# core_v1-1.net
KiCad netlist of a schematic drawn in EAGLE
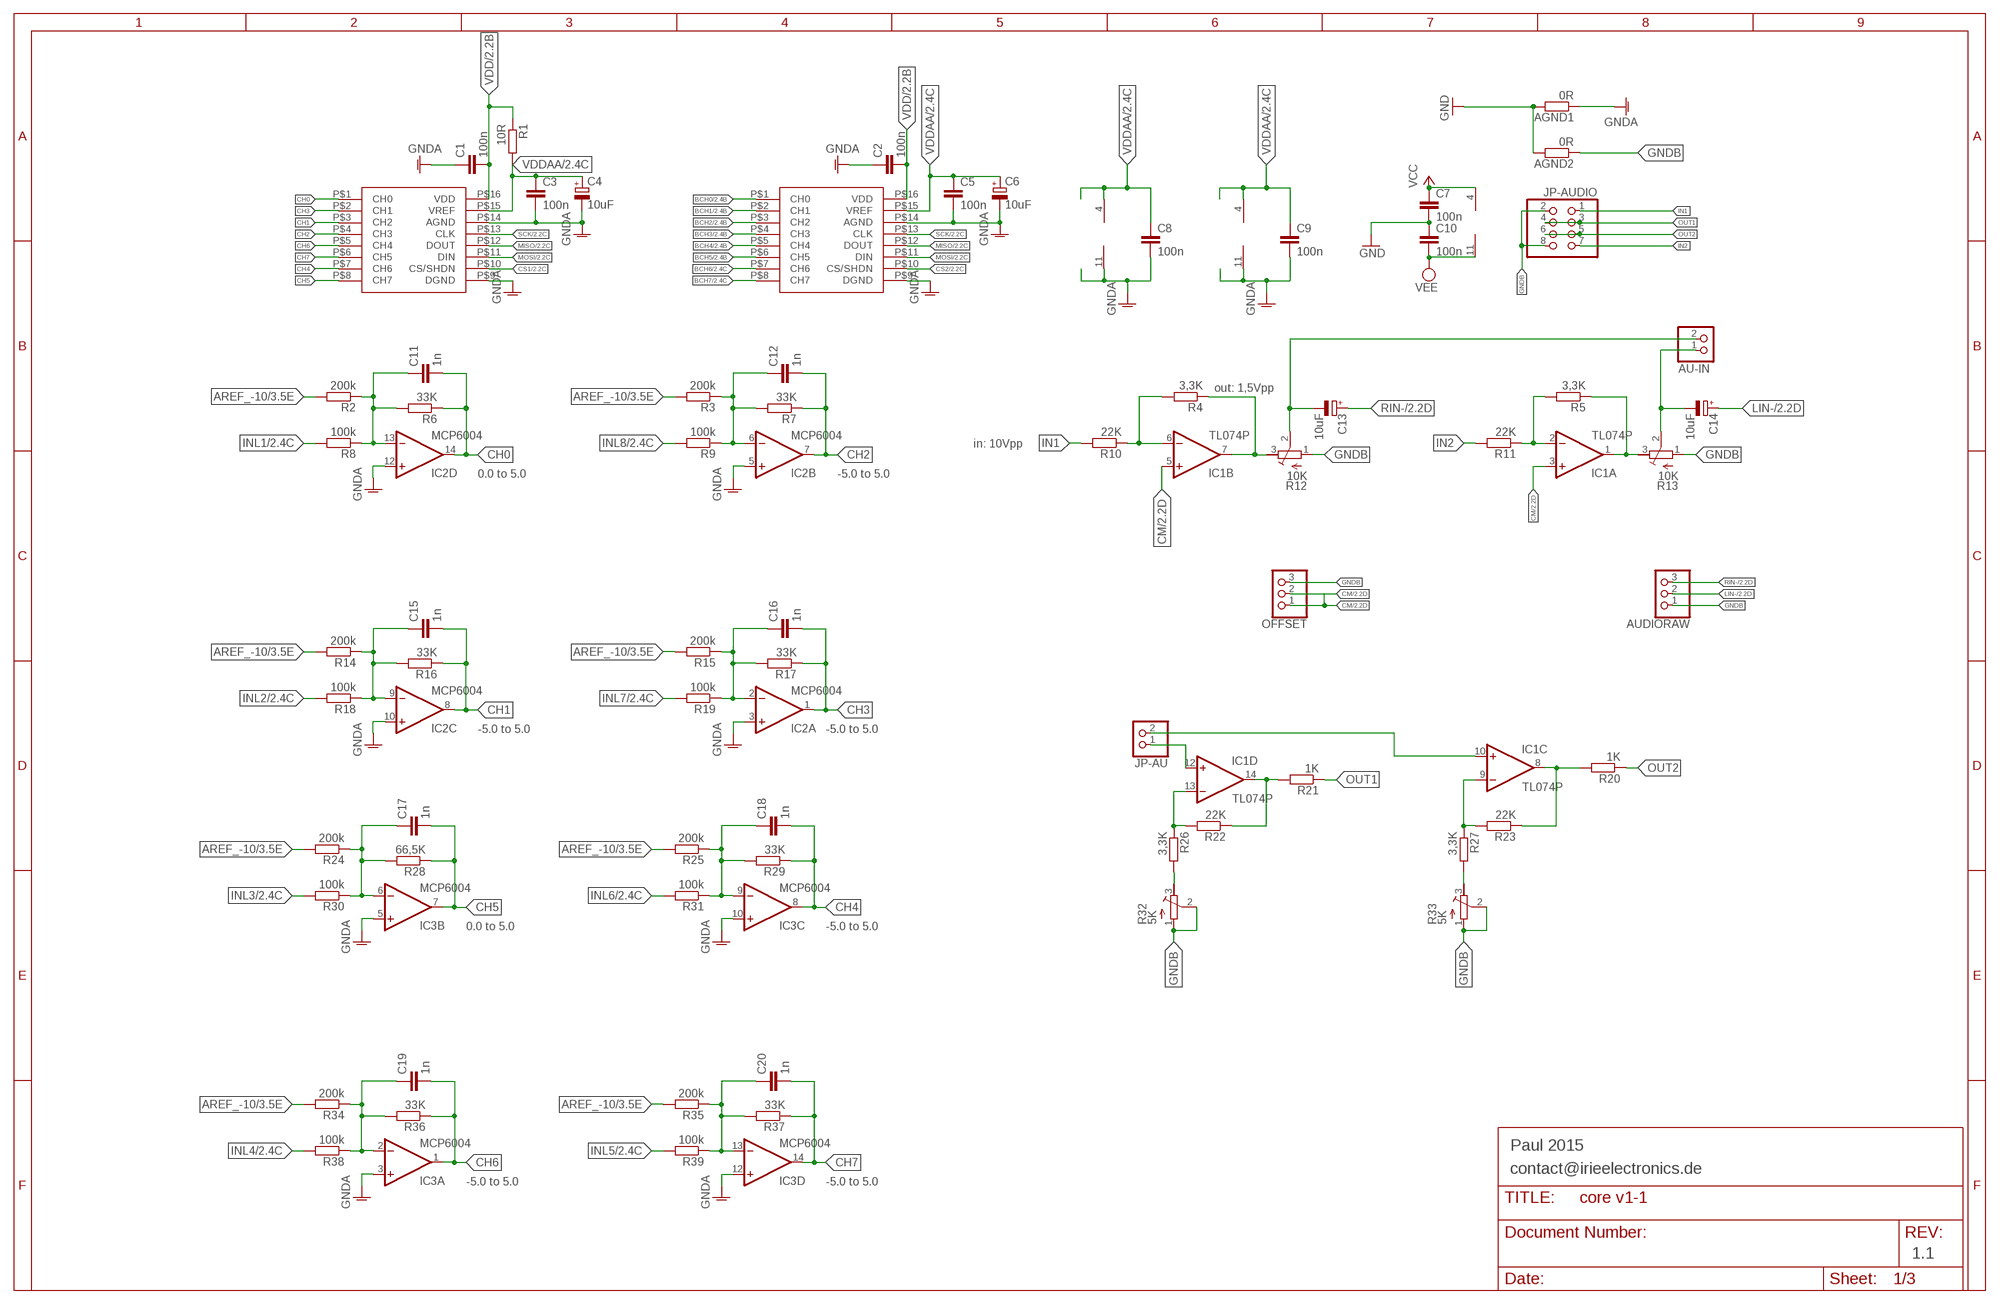
[diagram p0: schematic, sheet 1]
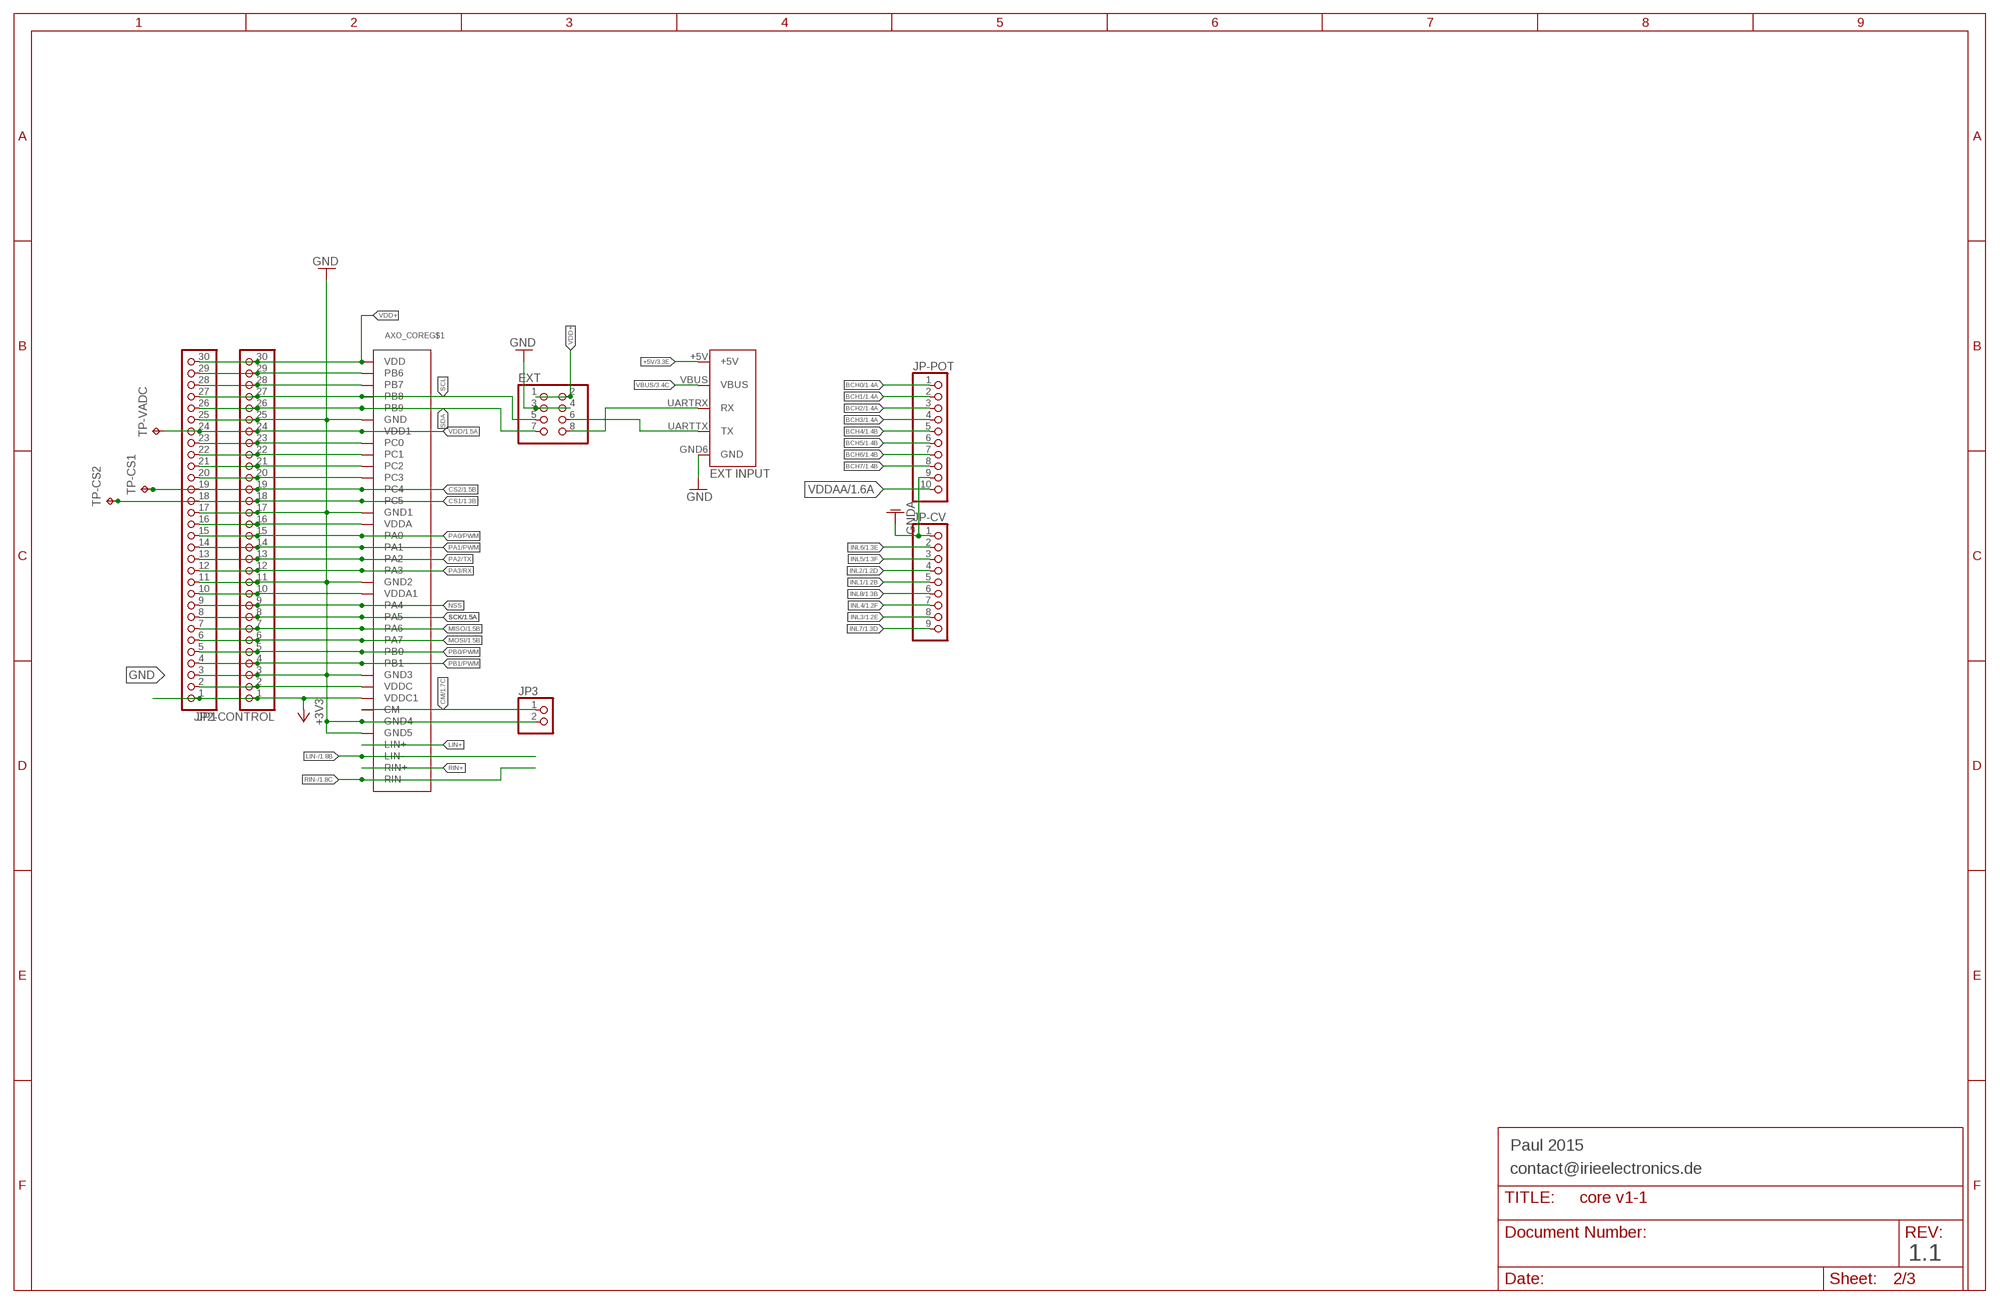
[diagram p1: schematic, sheet 2]
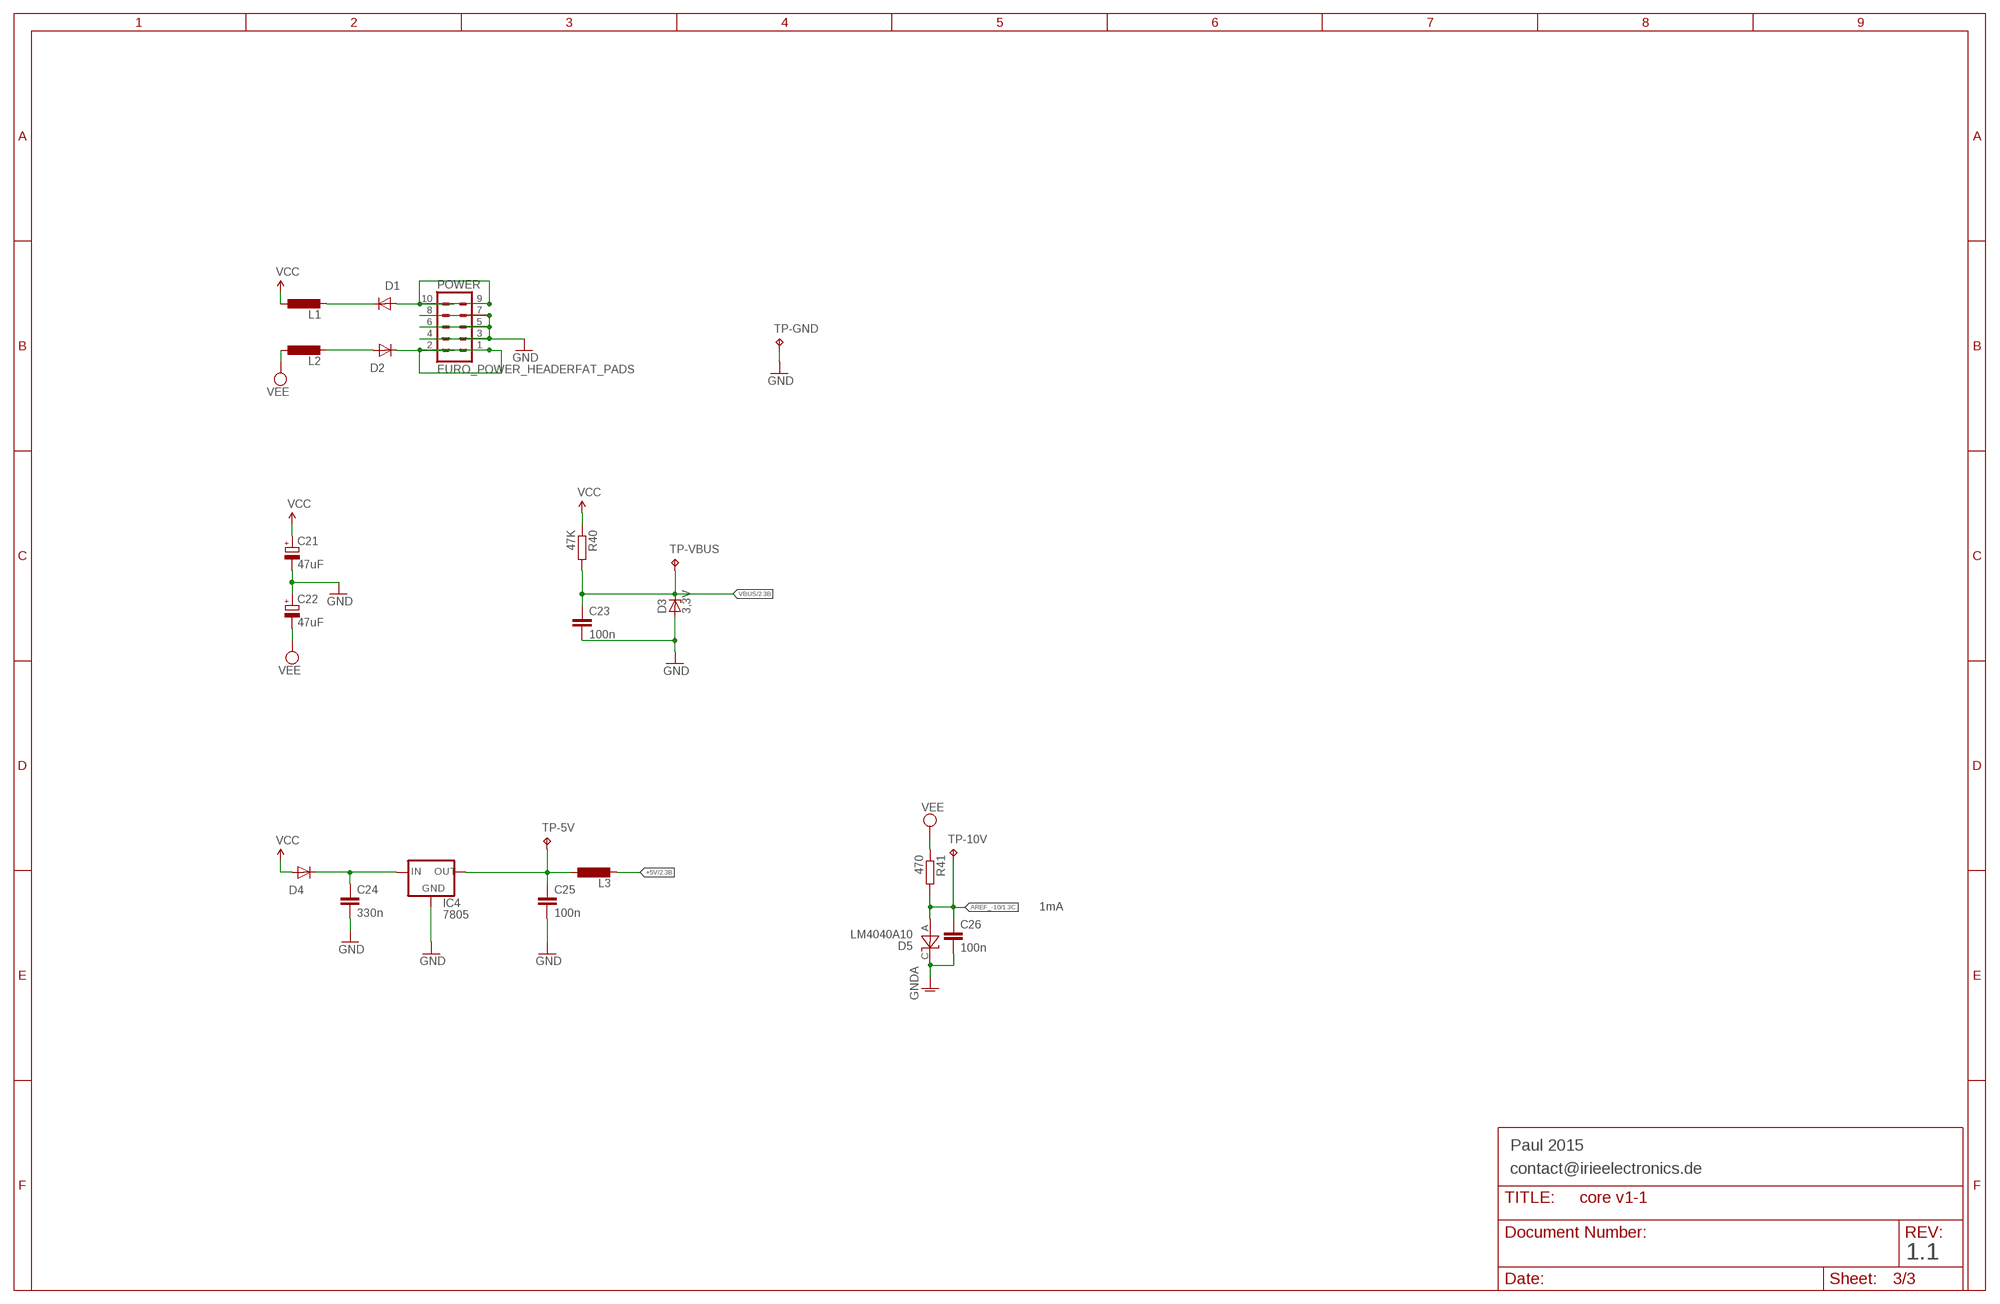
[diagram p2: schematic, sheet 3]

(export (version "E")
  (design (tool "Eeschema 10.0.6"))
  (components
    (comp (ref "C21")
      (value "47uF")
      (footprint "eagle-import:E2-5")
      (libsource (lib "eagle-import") (part "CPOL-EUE2-5"))
    )
    (comp (ref "C22")
      (value "47uF")
      (footprint "eagle-import:E2-5")
      (libsource (lib "eagle-import") (part "CPOL-EUE2-5"))
    )
    (comp (ref "C23")
      (value "100n")
      (footprint "eagle-import:C025-025X050")
      (libsource (lib "eagle-import") (part "C-EU025-025X050"))
    )
    (comp (ref "C24")
      (value "330n")
      (footprint "eagle-import:C025-025X050")
      (libsource (lib "eagle-import") (part "C-EU025-025X050"))
    )
    (comp (ref "C25")
      (value "100n")
      (footprint "eagle-import:C025-025X050")
      (libsource (lib "eagle-import") (part "C-EU025-025X050"))
    )
    (comp (ref "C26")
      (value "100n")
      (footprint "eagle-import:C025-025X050")
      (libsource (lib "eagle-import") (part "C-EU025-025X050"))
    )
    (comp (ref "D1")
      (value "1N5819")
      (footprint "eagle-import:DO35-10")
      (libsource (lib "eagle-import") (part "1N4148DO35-10"))
    )
    (comp (ref "D2")
      (value "1N5819")
      (footprint "eagle-import:DO35-10")
      (libsource (lib "eagle-import") (part "1N4148DO35-10"))
    )
    (comp (ref "D3")
      (value "3,3V")
      (footprint "eagle-import:DO35Z10")
      (libsource (lib "eagle-import") (part "1N821"))
    )
    (comp (ref "D4")
      (value "1N5819HW")
      (footprint "eagle-import:DO35-10")
      (libsource (lib "eagle-import") (part "1N4148DO35-10"))
    )
    (comp (ref "D5")
      (value "LM4040A10")
      (footprint "eagle-import:TO-92")
      (libsource (lib "eagle-import") (part "LM4040DIP"))
    )
    (comp (ref "IC4")
      (value "7805")
      (footprint "eagle-import:78MXXS")
      (libsource (lib "eagle-import") (part "78MXXS"))
    )
    (comp (ref "L1")
      (value "L-EU0207/10")
      (footprint "eagle-import:0207_10")
      (libsource (lib "eagle-import") (part "L-EU0207/10"))
    )
    (comp (ref "L2")
      (value "L-EU0207/10")
      (footprint "eagle-import:0207_10")
      (libsource (lib "eagle-import") (part "L-EU0207/10"))
    )
    (comp (ref "L3")
      (value "L-EU0207/10")
      (footprint "eagle-import:0207_10")
      (libsource (lib "eagle-import") (part "L-EU0207/10"))
    )
    (comp (ref "POWER")
      (value "EURO_POWER_HEADERFAT_PADS")
      (footprint "eagle-import:EURO_PWR_HEADER_FAT")
      (libsource (lib "eagle-import") (part "EURO_POWER_HEADERFAT_PADS"))
    )
    (comp (ref "R40")
      (value "47K")
      (footprint "eagle-import:0207_7")
      (libsource (lib "eagle-import") (part "R-EU_0207/7"))
    )
    (comp (ref "R41")
      (value "470")
      (footprint "eagle-import:0207_10")
      (libsource (lib "eagle-import") (part "R-EU_0207/10"))
    )
    (comp (ref "TP-5V")
      (value "TPTP10R")
      (footprint "eagle-import:TP10R")
      (libsource (lib "eagle-import") (part "TPTP10R"))
    )
    (comp (ref "TP-10V")
      (value "TPTP10R")
      (footprint "eagle-import:TP10R")
      (libsource (lib "eagle-import") (part "TPTP10R"))
    )
    (comp (ref "TP-GND")
      (value "TPPAD1-13")
      (footprint "eagle-import:P1-13")
      (libsource (lib "eagle-import") (part "TPPAD1-13"))
    )
    (comp (ref "TP-VBUS")
      (value "TPTP10R")
      (footprint "eagle-import:TP10R")
      (libsource (lib "eagle-import") (part "TPTP10R"))
    )
    (comp (ref "AGND1")
      (value "0R")
      (footprint "eagle-import:0207_7")
      (libsource (lib "eagle-import") (part "R-EU_0207/7"))
    )
    (comp (ref "AGND2")
      (value "0R")
      (footprint "eagle-import:0207_7")
      (libsource (lib "eagle-import") (part "R-EU_0207/7"))
    )
    (comp (ref "AU-IN")
      (value "PINHD-1X2_2.54-SMD-90°")
      (footprint "eagle-import:1X02SMD_90")
      (libsource (lib "eagle-import") (part "PINHD-1X2_2.54-SMD-90°"))
    )
    (comp (ref "AUDIORAW")
      (value "PINHD-1X3_2.54-SMD-90°")
      (footprint "eagle-import:1X03SMD_90")
      (libsource (lib "eagle-import") (part "PINHD-1X3_2.54-SMD-90°"))
    )
    (comp (ref "C1")
      (value "100n")
      (footprint "eagle-import:C025-025X050")
      (libsource (lib "eagle-import") (part "C-EU025-025X050"))
    )
    (comp (ref "C2")
      (value "100n")
      (footprint "eagle-import:C025-025X050")
      (libsource (lib "eagle-import") (part "C-EU025-025X050"))
    )
    (comp (ref "C3")
      (value "100n")
      (footprint "eagle-import:C025-025X050")
      (libsource (lib "eagle-import") (part "C-EU025-025X050"))
    )
    (comp (ref "C4")
      (value "10uF")
      (footprint "eagle-import:E1,8-4")
      (libsource (lib "eagle-import") (part "CPOL-EUE1.8-4"))
    )
    (comp (ref "C5")
      (value "100n")
      (footprint "eagle-import:C025-025X050")
      (libsource (lib "eagle-import") (part "C-EU025-025X050"))
    )
    (comp (ref "C6")
      (value "10uF")
      (footprint "eagle-import:E1,8-4")
      (libsource (lib "eagle-import") (part "CPOL-EUE1.8-4"))
    )
    (comp (ref "C7")
      (value "100n")
      (footprint "eagle-import:C025-025X050")
      (libsource (lib "eagle-import") (part "C-EU025-025X050"))
    )
    (comp (ref "C8")
      (value "100n")
      (footprint "eagle-import:C025-025X050")
      (libsource (lib "eagle-import") (part "C-EU025-025X050"))
    )
    (comp (ref "C9")
      (value "100n")
      (footprint "eagle-import:C025-025X050")
      (libsource (lib "eagle-import") (part "C-EU025-025X050"))
    )
    (comp (ref "C10")
      (value "100n")
      (footprint "eagle-import:C025-025X050")
      (libsource (lib "eagle-import") (part "C-EU025-025X050"))
    )
    (comp (ref "C11")
      (value "1n")
      (footprint "eagle-import:C050-025X075")
      (libsource (lib "eagle-import") (part "C-EU050-025X075"))
    )
    (comp (ref "C12")
      (value "1n")
      (footprint "eagle-import:C050-025X075")
      (libsource (lib "eagle-import") (part "C-EU050-025X075"))
    )
    (comp (ref "C13")
      (value "10uF")
      (footprint "eagle-import:E1,8-4")
      (libsource (lib "eagle-import") (part "CPOL-EUE1.8-4"))
    )
    (comp (ref "C14")
      (value "10uF")
      (footprint "eagle-import:E1,8-4")
      (libsource (lib "eagle-import") (part "CPOL-EUE1.8-4"))
    )
    (comp (ref "C15")
      (value "1n")
      (footprint "eagle-import:C050-025X075")
      (libsource (lib "eagle-import") (part "C-EU050-025X075"))
    )
    (comp (ref "C16")
      (value "1n")
      (footprint "eagle-import:C050-025X075")
      (libsource (lib "eagle-import") (part "C-EU050-025X075"))
    )
    (comp (ref "C17")
      (value "1n")
      (footprint "eagle-import:C050-025X075")
      (libsource (lib "eagle-import") (part "C-EU050-025X075"))
    )
    (comp (ref "C18")
      (value "1n")
      (footprint "eagle-import:C050-025X075")
      (libsource (lib "eagle-import") (part "C-EU050-025X075"))
    )
    (comp (ref "C19")
      (value "1n")
      (footprint "eagle-import:C050-025X075")
      (libsource (lib "eagle-import") (part "C-EU050-025X075"))
    )
    (comp (ref "C20")
      (value "1n")
      (footprint "eagle-import:C050-025X075")
      (libsource (lib "eagle-import") (part "C-EU050-025X075"))
    )
    (comp (ref "IC1")
      (value "TL074P")
      (footprint "eagle-import:DIL14")
      (libsource (lib "eagle-import") (part "TL074P"))
    )
    (comp (ref "IC2")
      (value "MCP6004")
      (footprint "eagle-import:DIL14")
      (libsource (lib "eagle-import") (part "TL074P"))
    )
    (comp (ref "IC3")
      (value "MCP6004")
      (footprint "eagle-import:DIL14")
      (libsource (lib "eagle-import") (part "TL074P"))
    )
    (comp (ref "JP-AU")
      (value "PINHD-1X2_2.54")
      (footprint "eagle-import:1X02")
      (libsource (lib "eagle-import") (part "PINHD-1X2_2.54"))
    )
    (comp (ref "JP-AUDIO")
      (value "PINHD-2X4_2.54")
      (footprint "eagle-import:2X04")
      (libsource (lib "eagle-import") (part "PINHD-2X4_2.54"))
    )
    (comp (ref "OFFSET")
      (value "PINHD-1X3_2.54-SMD-90°")
      (footprint "eagle-import:1X03SMD_90")
      (libsource (lib "eagle-import") (part "PINHD-1X3_2.54-SMD-90°"))
    )
    (comp (ref "R1")
      (value "10R")
      (footprint "eagle-import:0207_7")
      (libsource (lib "eagle-import") (part "R-EU_0207/7"))
    )
    (comp (ref "R2")
      (value "200k")
      (footprint "eagle-import:0207_7")
      (libsource (lib "eagle-import") (part "R-EU_0207/7"))
    )
    (comp (ref "R3")
      (value "200k")
      (footprint "eagle-import:0207_7")
      (libsource (lib "eagle-import") (part "R-EU_0207/7"))
    )
    (comp (ref "R4")
      (value "3,3K")
      (footprint "eagle-import:0207_7")
      (libsource (lib "eagle-import") (part "R-EU_0207/7"))
    )
    (comp (ref "R5")
      (value "3,3K")
      (footprint "eagle-import:0207_7")
      (libsource (lib "eagle-import") (part "R-EU_0207/7"))
    )
    (comp (ref "R6")
      (value "33K")
      (footprint "eagle-import:0207_7")
      (libsource (lib "eagle-import") (part "R-EU_0207/7"))
    )
    (comp (ref "R7")
      (value "33K")
      (footprint "eagle-import:0207_7")
      (libsource (lib "eagle-import") (part "R-EU_0207/7"))
    )
    (comp (ref "R8")
      (value "100k")
      (footprint "eagle-import:0207_7")
      (libsource (lib "eagle-import") (part "R-EU_0207/7"))
    )
    (comp (ref "R9")
      (value "100k")
      (footprint "eagle-import:0207_7")
      (libsource (lib "eagle-import") (part "R-EU_0207/7"))
    )
    (comp (ref "R10")
      (value "22K")
      (footprint "eagle-import:0207_7")
      (libsource (lib "eagle-import") (part "R-EU_0207/7"))
    )
    (comp (ref "R11")
      (value "22K")
      (footprint "eagle-import:0207_7")
      (libsource (lib "eagle-import") (part "R-EU_0207/7"))
    )
    (comp (ref "R12")
      (value "10K")
      (footprint "eagle-import:RTRIM3296P")
      (libsource (lib "eagle-import") (part "R-TRIMM3296P"))
    )
    (comp (ref "R13")
      (value "10K")
      (footprint "eagle-import:RTRIM3296P")
      (libsource (lib "eagle-import") (part "R-TRIMM3296P"))
    )
    (comp (ref "R14")
      (value "200k")
      (footprint "eagle-import:0207_7")
      (libsource (lib "eagle-import") (part "R-EU_0207/7"))
    )
    (comp (ref "R15")
      (value "200k")
      (footprint "eagle-import:0207_7")
      (libsource (lib "eagle-import") (part "R-EU_0207/7"))
    )
    (comp (ref "R16")
      (value "33K")
      (footprint "eagle-import:0207_7")
      (libsource (lib "eagle-import") (part "R-EU_0207/7"))
    )
    (comp (ref "R17")
      (value "33K")
      (footprint "eagle-import:0207_7")
      (libsource (lib "eagle-import") (part "R-EU_0207/7"))
    )
    (comp (ref "R18")
      (value "100k")
      (footprint "eagle-import:0207_7")
      (libsource (lib "eagle-import") (part "R-EU_0207/7"))
    )
    (comp (ref "R19")
      (value "100k")
      (footprint "eagle-import:0207_10")
      (libsource (lib "eagle-import") (part "R-EU_0207/10"))
    )
    (comp (ref "R20")
      (value "1K")
      (footprint "eagle-import:0207_7")
      (libsource (lib "eagle-import") (part "R-EU_0207/7"))
    )
    (comp (ref "R21")
      (value "1K")
      (footprint "eagle-import:0207_7")
      (libsource (lib "eagle-import") (part "R-EU_0207/7"))
    )
    (comp (ref "R22")
      (value "22K")
      (footprint "eagle-import:0207_10")
      (libsource (lib "eagle-import") (part "R-EU_0207/10"))
    )
    (comp (ref "R23")
      (value "22K")
      (footprint "eagle-import:0207_7")
      (libsource (lib "eagle-import") (part "R-EU_0207/7"))
    )
    (comp (ref "R24")
      (value "200k")
      (footprint "eagle-import:0207_10")
      (libsource (lib "eagle-import") (part "R-EU_0207/10"))
    )
    (comp (ref "R25")
      (value "200k")
      (footprint "eagle-import:0207_7")
      (libsource (lib "eagle-import") (part "R-EU_0207/7"))
    )
    (comp (ref "R26")
      (value "3,3K")
      (footprint "eagle-import:0207_10")
      (libsource (lib "eagle-import") (part "R-EU_0207/10"))
    )
    (comp (ref "R27")
      (value "3,3K")
      (footprint "eagle-import:0207_7")
      (libsource (lib "eagle-import") (part "R-EU_0207/7"))
    )
    (comp (ref "R28")
      (value "66,5K")
      (footprint "eagle-import:0207_7")
      (libsource (lib "eagle-import") (part "R-EU_0207/7"))
    )
    (comp (ref "R29")
      (value "33K")
      (footprint "eagle-import:0207_7")
      (libsource (lib "eagle-import") (part "R-EU_0207/7"))
    )
    (comp (ref "R30")
      (value "100k")
      (footprint "eagle-import:0207_7")
      (libsource (lib "eagle-import") (part "R-EU_0207/7"))
    )
    (comp (ref "R31")
      (value "100k")
      (footprint "eagle-import:0207_7")
      (libsource (lib "eagle-import") (part "R-EU_0207/7"))
    )
    (comp (ref "R32")
      (value "5K")
      (footprint "eagle-import:RTRIM3296P")
      (libsource (lib "eagle-import") (part "R-TRIMM3296P"))
    )
    (comp (ref "R33")
      (value "5K")
      (footprint "eagle-import:RTRIM3296P")
      (libsource (lib "eagle-import") (part "R-TRIMM3296P"))
    )
    (comp (ref "R34")
      (value "200k")
      (footprint "eagle-import:0207_10")
      (libsource (lib "eagle-import") (part "R-EU_0207/10"))
    )
    (comp (ref "R35")
      (value "200k")
      (footprint "eagle-import:0207_7")
      (libsource (lib "eagle-import") (part "R-EU_0207/7"))
    )
    (comp (ref "R36")
      (value "33K")
      (footprint "eagle-import:0207_7")
      (libsource (lib "eagle-import") (part "R-EU_0207/7"))
    )
    (comp (ref "R37")
      (value "33K")
      (footprint "eagle-import:0207_7")
      (libsource (lib "eagle-import") (part "R-EU_0207/7"))
    )
    (comp (ref "R38")
      (value "100k")
      (footprint "eagle-import:0207_7")
      (libsource (lib "eagle-import") (part "R-EU_0207/7"))
    )
    (comp (ref "R39")
      (value "100k")
      (footprint "eagle-import:0207_7")
      (libsource (lib "eagle-import") (part "R-EU_0207/7"))
    )
    (comp (ref "U$1")
      (value "MCP3208_DIP")
      (footprint "eagle-import:MCP2308")
      (libsource (lib "eagle-import") (part "MCP3208_DIP"))
    )
    (comp (ref "U$2")
      (value "MCP3208_DIP")
      (footprint "eagle-import:MCP2308")
      (libsource (lib "eagle-import") (part "MCP3208_DIP"))
    )
    (comp (ref "AXO_CORE")
      (value "AXO-CORE")
      (footprint "eagle-import:AXOLOTI-CORE")
      (libsource (lib "eagle-import") (part "AXOLOTI-CORE"))
    )
    (comp (ref "EXT")
      (value "PINHD-2X4_2.54")
      (footprint "eagle-import:2X04")
      (libsource (lib "eagle-import") (part "PINHD-2X4_2.54"))
    )
    (comp (ref "JP-CV")
      (value "PINHD-1X9_2.54")
      (footprint "eagle-import:1X09")
      (libsource (lib "eagle-import") (part "PINHD-1X9_2.54"))
    )
    (comp (ref "JP-POT")
      (value "PINHD-1X10_2.54")
      (footprint "eagle-import:1X10")
      (libsource (lib "eagle-import") (part "PINHD-1X10_2.54"))
    )
    (comp (ref "JP1")
      (value "PINHD-1X30")
      (footprint "eagle-import:1X30")
      (libsource (lib "eagle-import") (part "PINHD-1X30"))
    )
    (comp (ref "JP2-CONTROL")
      (value "PINHD-1X30")
      (footprint "eagle-import:1X30")
      (libsource (lib "eagle-import") (part "PINHD-1X30"))
    )
    (comp (ref "JP3")
      (value "PINHD-1X2_2.54")
      (footprint "eagle-import:1X02")
      (libsource (lib "eagle-import") (part "PINHD-1X2_2.54"))
    )
    (comp (ref "TP-CS1")
      (value "TPTP10R")
      (footprint "eagle-import:TP10R")
      (libsource (lib "eagle-import") (part "TPTP10R"))
    )
    (comp (ref "TP-CS2")
      (value "TPTP10R")
      (footprint "eagle-import:TP10R")
      (libsource (lib "eagle-import") (part "TPTP10R"))
    )
    (comp (ref "TP-VADC")
      (value "TPTP10R")
      (footprint "eagle-import:TP10R")
      (libsource (lib "eagle-import") (part "TPTP10R"))
    )
  )
  (nets
    (net (code "1") (name "+3V3") (class "Default")
      (node (ref "AXO_CORE") (pin "VDDC1") (pinfunction "VDDC1_VDDC1") (pintype "bidirectional"))
      (node (ref "JP1") (pin "1") (pinfunction "1_1") (pintype "passive"))
      (node (ref "JP2-CONTROL") (pin "1") (pinfunction "1_1") (pintype "passive"))
    )
    (net (code "2") (name "+5V") (class "Default")
      (node (ref "AXO_CORE") (pin "+5V") (pinfunction "+5V_+5V") (pintype "bidirectional"))
      (node (ref "L3") (pin "2") (pinfunction "2_2") (pintype "passive"))
    )
    (net (code "3") (name "AREF_-10") (class "Default")
      (node (ref "C26") (pin "1") (pinfunction "1_1") (pintype "passive"))
      (node (ref "D5") (pin "A") (pinfunction "A_A") (pintype "output"))
      (node (ref "R14") (pin "2") (pinfunction "2_2") (pintype "passive"))
      (node (ref "R15") (pin "2") (pinfunction "2_2") (pintype "passive"))
      (node (ref "R2") (pin "2") (pinfunction "2_2") (pintype "passive"))
      (node (ref "R24") (pin "2") (pinfunction "2_2") (pintype "passive"))
      (node (ref "R25") (pin "2") (pinfunction "2_2") (pintype "passive"))
      (node (ref "R3") (pin "2") (pinfunction "2_2") (pintype "passive"))
      (node (ref "R34") (pin "2") (pinfunction "2_2") (pintype "passive"))
      (node (ref "R35") (pin "2") (pinfunction "2_2") (pintype "passive"))
      (node (ref "R41") (pin "2") (pinfunction "2_2") (pintype "passive"))
      (node (ref "TP-10V") (pin "TP") (pinfunction "TP_TP") (pintype "input"))
    )
    (net (code "4") (name "BCH0") (class "Default")
      (node (ref "JP-POT") (pin "1") (pinfunction "1_1") (pintype "passive"))
      (node (ref "U$2") (pin "P$1") (pinfunction "CH0_P$1") (pintype "bidirectional"))
    )
    (net (code "5") (name "BCH1") (class "Default")
      (node (ref "JP-POT") (pin "2") (pinfunction "2_2") (pintype "passive"))
      (node (ref "U$2") (pin "P$2") (pinfunction "CH1_P$2") (pintype "bidirectional"))
    )
    (net (code "6") (name "BCH2") (class "Default")
      (node (ref "JP-POT") (pin "3") (pinfunction "3_3") (pintype "passive"))
      (node (ref "U$2") (pin "P$3") (pinfunction "CH2_P$3") (pintype "bidirectional"))
    )
    (net (code "7") (name "BCH3") (class "Default")
      (node (ref "JP-POT") (pin "4") (pinfunction "4_4") (pintype "passive"))
      (node (ref "U$2") (pin "P$4") (pinfunction "CH3_P$4") (pintype "bidirectional"))
    )
    (net (code "8") (name "BCH4") (class "Default")
      (node (ref "JP-POT") (pin "5") (pinfunction "5_5") (pintype "passive"))
      (node (ref "U$2") (pin "P$5") (pinfunction "CH4_P$5") (pintype "bidirectional"))
    )
    (net (code "9") (name "BCH5") (class "Default")
      (node (ref "JP-POT") (pin "6") (pinfunction "6_6") (pintype "passive"))
      (node (ref "U$2") (pin "P$6") (pinfunction "CH5_P$6") (pintype "bidirectional"))
    )
    (net (code "10") (name "BCH6") (class "Default")
      (node (ref "JP-POT") (pin "7") (pinfunction "7_7") (pintype "passive"))
      (node (ref "U$2") (pin "P$7") (pinfunction "CH6_P$7") (pintype "bidirectional"))
    )
    (net (code "11") (name "BCH7") (class "Default")
      (node (ref "JP-POT") (pin "8") (pinfunction "8_8") (pintype "passive"))
      (node (ref "U$2") (pin "P$8") (pinfunction "CH7_P$8") (pintype "bidirectional"))
    )
    (net (code "12") (name "CH0") (class "Default")
      (node (ref "C11") (pin "2") (pinfunction "2_2") (pintype "passive"))
      (node (ref "IC2") (pin "14") (pinfunction "OUT_14") (pintype "output"))
      (node (ref "R6") (pin "1") (pinfunction "1_1") (pintype "passive"))
      (node (ref "U$1") (pin "P$1") (pinfunction "CH0_P$1") (pintype "bidirectional"))
    )
    (net (code "13") (name "CH1") (class "Default")
      (node (ref "C15") (pin "2") (pinfunction "2_2") (pintype "passive"))
      (node (ref "IC2") (pin "8") (pinfunction "OUT_8") (pintype "output"))
      (node (ref "R16") (pin "1") (pinfunction "1_1") (pintype "passive"))
      (node (ref "U$1") (pin "P$3") (pinfunction "CH2_P$3") (pintype "bidirectional"))
    )
    (net (code "14") (name "CH2") (class "Default")
      (node (ref "C12") (pin "2") (pinfunction "2_2") (pintype "passive"))
      (node (ref "IC2") (pin "7") (pinfunction "OUT_7") (pintype "output"))
      (node (ref "R7") (pin "1") (pinfunction "1_1") (pintype "passive"))
      (node (ref "U$1") (pin "P$4") (pinfunction "CH3_P$4") (pintype "bidirectional"))
    )
    (net (code "15") (name "CH3") (class "Default")
      (node (ref "C16") (pin "2") (pinfunction "2_2") (pintype "passive"))
      (node (ref "IC2") (pin "1") (pinfunction "OUT_1") (pintype "output"))
      (node (ref "R17") (pin "1") (pinfunction "1_1") (pintype "passive"))
      (node (ref "U$1") (pin "P$2") (pinfunction "CH1_P$2") (pintype "bidirectional"))
    )
    (net (code "16") (name "CH4") (class "Default")
      (node (ref "C18") (pin "2") (pinfunction "2_2") (pintype "passive"))
      (node (ref "IC3") (pin "8") (pinfunction "OUT_8") (pintype "output"))
      (node (ref "R29") (pin "1") (pinfunction "1_1") (pintype "passive"))
      (node (ref "U$1") (pin "P$7") (pinfunction "CH6_P$7") (pintype "bidirectional"))
    )
    (net (code "17") (name "CH5") (class "Default")
      (node (ref "C17") (pin "2") (pinfunction "2_2") (pintype "passive"))
      (node (ref "IC3") (pin "7") (pinfunction "OUT_7") (pintype "output"))
      (node (ref "R28") (pin "1") (pinfunction "1_1") (pintype "passive"))
      (node (ref "U$1") (pin "P$8") (pinfunction "CH7_P$8") (pintype "bidirectional"))
    )
    (net (code "18") (name "CH6") (class "Default")
      (node (ref "C19") (pin "2") (pinfunction "2_2") (pintype "passive"))
      (node (ref "IC3") (pin "1") (pinfunction "OUT_1") (pintype "output"))
      (node (ref "R36") (pin "1") (pinfunction "1_1") (pintype "passive"))
      (node (ref "U$1") (pin "P$5") (pinfunction "CH4_P$5") (pintype "bidirectional"))
    )
    (net (code "19") (name "CH7") (class "Default")
      (node (ref "C20") (pin "2") (pinfunction "2_2") (pintype "passive"))
      (node (ref "IC3") (pin "14") (pinfunction "OUT_14") (pintype "output"))
      (node (ref "R37") (pin "1") (pinfunction "1_1") (pintype "passive"))
      (node (ref "U$1") (pin "P$6") (pinfunction "CH5_P$6") (pintype "bidirectional"))
    )
    (net (code "20") (name "CM") (class "Default")
      (node (ref "AXO_CORE") (pin "CM") (pinfunction "CM_CM") (pintype "bidirectional"))
      (node (ref "IC1") (pin "3") (pinfunction "+IN_3") (pintype "input"))
      (node (ref "IC1") (pin "5") (pinfunction "+IN_5") (pintype "input"))
      (node (ref "JP3") (pin "1") (pinfunction "1_1") (pintype "passive"))
      (node (ref "OFFSET") (pin "1") (pinfunction "1_1") (pintype "passive"))
      (node (ref "OFFSET") (pin "2") (pinfunction "2_2") (pintype "passive"))
    )
    (net (code "21") (name "CS1") (class "Default")
      (node (ref "AXO_CORE") (pin "PC5") (pinfunction "PC5_PC5") (pintype "bidirectional"))
      (node (ref "JP1") (pin "18") (pinfunction "18_18") (pintype "passive"))
      (node (ref "JP2-CONTROL") (pin "18") (pinfunction "18_18") (pintype "passive"))
      (node (ref "TP-CS2") (pin "TP") (pinfunction "TP_TP") (pintype "input"))
      (node (ref "U$1") (pin "P$10") (pinfunction "CS/SHDN_P$10") (pintype "bidirectional"))
    )
    (net (code "22") (name "CS2") (class "Default")
      (node (ref "AXO_CORE") (pin "PC4") (pinfunction "PC4_PC4") (pintype "bidirectional"))
      (node (ref "JP1") (pin "19") (pinfunction "19_19") (pintype "passive"))
      (node (ref "JP2-CONTROL") (pin "19") (pinfunction "19_19") (pintype "passive"))
      (node (ref "TP-CS1") (pin "TP") (pinfunction "TP_TP") (pintype "input"))
      (node (ref "U$2") (pin "P$10") (pinfunction "CS/SHDN_P$10") (pintype "bidirectional"))
    )
    (net (code "23") (name "GND") (class "Default")
      (node (ref "AGND1") (pin "2") (pinfunction "2_2") (pintype "passive"))
      (node (ref "AGND2") (pin "2") (pinfunction "2_2") (pintype "passive"))
      (node (ref "AXO_CORE") (pin "GND") (pinfunction "GND_GND") (pintype "bidirectional"))
      (node (ref "AXO_CORE") (pin "GND1") (pinfunction "GND1_GND1") (pintype "bidirectional"))
      (node (ref "AXO_CORE") (pin "GND2") (pinfunction "GND3_GND2") (pintype "bidirectional"))
      (node (ref "AXO_CORE") (pin "GND3") (pinfunction "GND2_GND3") (pintype "bidirectional"))
      (node (ref "AXO_CORE") (pin "GND4") (pinfunction "GND4_GND4") (pintype "bidirectional"))
      (node (ref "AXO_CORE") (pin "GND5") (pinfunction "GND5_GND5") (pintype "bidirectional"))
      (node (ref "AXO_CORE") (pin "GND6") (pinfunction "GND_GND6") (pintype "bidirectional"))
      (node (ref "C10") (pin "1") (pinfunction "1_1") (pintype "passive"))
      (node (ref "C21") (pin "-") (pinfunction "-_-") (pintype "passive"))
      (node (ref "C22") (pin "+") (pinfunction "+_+") (pintype "passive"))
      (node (ref "C23") (pin "2") (pinfunction "2_2") (pintype "passive"))
      (node (ref "C24") (pin "2") (pinfunction "2_2") (pintype "passive"))
      (node (ref "C25") (pin "2") (pinfunction "2_2") (pintype "passive"))
      (node (ref "C7") (pin "2") (pinfunction "2_2") (pintype "passive"))
      (node (ref "D3") (pin "A") (pinfunction "A_A") (pintype "passive"))
      (node (ref "EXT") (pin "3") (pinfunction "3_3") (pintype "passive"))
      (node (ref "EXT") (pin "4") (pinfunction "4_4") (pintype "passive"))
      (node (ref "IC4") (pin "GND") (pinfunction "GND_GND") (pintype "input"))
      (node (ref "JP1") (pin "11") (pinfunction "11_11") (pintype "passive"))
      (node (ref "JP1") (pin "17") (pinfunction "17_17") (pintype "passive"))
      (node (ref "JP1") (pin "25") (pinfunction "25_25") (pintype "passive"))
      (node (ref "JP1") (pin "3") (pinfunction "3_3") (pintype "passive"))
      (node (ref "JP2-CONTROL") (pin "11") (pinfunction "11_11") (pintype "passive"))
      (node (ref "JP2-CONTROL") (pin "17") (pinfunction "17_17") (pintype "passive"))
      (node (ref "JP2-CONTROL") (pin "25") (pinfunction "25_25") (pintype "passive"))
      (node (ref "JP2-CONTROL") (pin "3") (pinfunction "3_3") (pintype "passive"))
      (node (ref "JP3") (pin "2") (pinfunction "2_2") (pintype "passive"))
      (node (ref "POWER") (pin "3") (pinfunction "3_3") (pintype "passive"))
      (node (ref "POWER") (pin "4") (pinfunction "4_4") (pintype "passive"))
      (node (ref "POWER") (pin "5") (pinfunction "5_5") (pintype "passive"))
      (node (ref "POWER") (pin "6") (pinfunction "6_6") (pintype "passive"))
      (node (ref "POWER") (pin "7") (pinfunction "7_7") (pintype "passive"))
      (node (ref "POWER") (pin "8") (pinfunction "8_8") (pintype "passive"))
      (node (ref "TP-GND") (pin "TP") (pinfunction "TP_TP") (pintype "input"))
    )
    (net (code "24") (name "GNDA") (class "Default")
      (node (ref "AGND1") (pin "1") (pinfunction "1_1") (pintype "passive"))
      (node (ref "C1") (pin "1") (pinfunction "1_1") (pintype "passive"))
      (node (ref "C2") (pin "1") (pinfunction "1_1") (pintype "passive"))
      (node (ref "C26") (pin "2") (pinfunction "2_2") (pintype "passive"))
      (node (ref "C3") (pin "2") (pinfunction "2_2") (pintype "passive"))
      (node (ref "C4") (pin "-") (pinfunction "-_-") (pintype "passive"))
      (node (ref "C5") (pin "2") (pinfunction "2_2") (pintype "passive"))
      (node (ref "C6") (pin "-") (pinfunction "-_-") (pintype "passive"))
      (node (ref "C8") (pin "2") (pinfunction "2_2") (pintype "passive"))
      (node (ref "C9") (pin "2") (pinfunction "2_2") (pintype "passive"))
      (node (ref "D5") (pin "C") (pinfunction "C_C") (pintype "input"))
      (node (ref "IC2") (pin "10") (pinfunction "+IN_10") (pintype "input"))
      (node (ref "IC2") (pin "11") (pinfunction "V-_11") (pintype "power_in"))
      (node (ref "IC2") (pin "12") (pinfunction "+IN_12") (pintype "input"))
      (node (ref "IC2") (pin "3") (pinfunction "+IN_3") (pintype "input"))
      (node (ref "IC2") (pin "5") (pinfunction "+IN_5") (pintype "input"))
      (node (ref "IC3") (pin "10") (pinfunction "+IN_10") (pintype "input"))
      (node (ref "IC3") (pin "11") (pinfunction "V-_11") (pintype "power_in"))
      (node (ref "IC3") (pin "12") (pinfunction "+IN_12") (pintype "input"))
      (node (ref "IC3") (pin "3") (pinfunction "+IN_3") (pintype "input"))
      (node (ref "IC3") (pin "5") (pinfunction "+IN_5") (pintype "input"))
      (node (ref "JP-CV") (pin "1") (pinfunction "1_1") (pintype "passive"))
      (node (ref "JP-POT") (pin "9") (pinfunction "9_9") (pintype "passive"))
      (node (ref "U$1") (pin "P$14") (pinfunction "AGND_P$14") (pintype "bidirectional"))
      (node (ref "U$1") (pin "P$9") (pinfunction "DGND_P$9") (pintype "bidirectional"))
      (node (ref "U$2") (pin "P$14") (pinfunction "AGND_P$14") (pintype "bidirectional"))
      (node (ref "U$2") (pin "P$9") (pinfunction "DGND_P$9") (pintype "bidirectional"))
    )
    (net (code "25") (name "GNDB") (class "Default")
      (node (ref "AGND2") (pin "1") (pinfunction "1_1") (pintype "passive"))
      (node (ref "AUDIORAW") (pin "1") (pinfunction "1_1") (pintype "passive"))
      (node (ref "JP-AUDIO") (pin "2") (pinfunction "2_2") (pintype "passive"))
      (node (ref "JP-AUDIO") (pin "8") (pinfunction "8_8") (pintype "passive"))
      (node (ref "OFFSET") (pin "3") (pinfunction "3_3") (pintype "passive"))
      (node (ref "R12") (pin "1") (pinfunction "E_1") (pintype "passive"))
      (node (ref "R13") (pin "1") (pinfunction "E_1") (pintype "passive"))
      (node (ref "R32") (pin "1") (pinfunction "E_1") (pintype "passive"))
      (node (ref "R32") (pin "2") (pinfunction "S_2") (pintype "passive"))
      (node (ref "R33") (pin "1") (pinfunction "E_1") (pintype "passive"))
      (node (ref "R33") (pin "2") (pinfunction "S_2") (pintype "passive"))
    )
    (net (code "26") (name "IN1") (class "Default")
      (node (ref "JP-AUDIO") (pin "1") (pinfunction "1_1") (pintype "passive"))
      (node (ref "R10") (pin "2") (pinfunction "2_2") (pintype "passive"))
    )
    (net (code "27") (name "IN2") (class "Default")
      (node (ref "JP-AUDIO") (pin "7") (pinfunction "7_7") (pintype "passive"))
      (node (ref "R11") (pin "2") (pinfunction "2_2") (pintype "passive"))
    )
    (net (code "28") (name "INL1") (class "Default")
      (node (ref "JP-CV") (pin "5") (pinfunction "5_5") (pintype "passive"))
      (node (ref "R8") (pin "2") (pinfunction "2_2") (pintype "passive"))
    )
    (net (code "29") (name "INL2") (class "Default")
      (node (ref "JP-CV") (pin "4") (pinfunction "4_4") (pintype "passive"))
      (node (ref "R18") (pin "2") (pinfunction "2_2") (pintype "passive"))
    )
    (net (code "30") (name "INL3") (class "Default")
      (node (ref "JP-CV") (pin "8") (pinfunction "8_8") (pintype "passive"))
      (node (ref "R30") (pin "2") (pinfunction "2_2") (pintype "passive"))
    )
    (net (code "31") (name "INL4") (class "Default")
      (node (ref "JP-CV") (pin "7") (pinfunction "7_7") (pintype "passive"))
      (node (ref "R38") (pin "2") (pinfunction "2_2") (pintype "passive"))
    )
    (net (code "32") (name "INL5") (class "Default")
      (node (ref "JP-CV") (pin "3") (pinfunction "3_3") (pintype "passive"))
      (node (ref "R39") (pin "2") (pinfunction "2_2") (pintype "passive"))
    )
    (net (code "33") (name "INL6") (class "Default")
      (node (ref "JP-CV") (pin "2") (pinfunction "2_2") (pintype "passive"))
      (node (ref "R31") (pin "2") (pinfunction "2_2") (pintype "passive"))
    )
    (net (code "34") (name "INL7") (class "Default")
      (node (ref "JP-CV") (pin "9") (pinfunction "9_9") (pintype "passive"))
      (node (ref "R19") (pin "2") (pinfunction "2_2") (pintype "passive"))
    )
    (net (code "35") (name "INL8") (class "Default")
      (node (ref "JP-CV") (pin "6") (pinfunction "6_6") (pintype "passive"))
      (node (ref "R9") (pin "2") (pinfunction "2_2") (pintype "passive"))
    )
    (net (code "36") (name "LIN+") (class "Default")
      (node (ref "AXO_CORE") (pin "LIN+") (pinfunction "LIN+_LIN+") (pintype "bidirectional"))
    )
    (net (code "37") (name "LIN-") (class "Default")
      (node (ref "AUDIORAW") (pin "2") (pinfunction "2_2") (pintype "passive"))
      (node (ref "AXO_CORE") (pin "LIN-") (pinfunction "LIN-_LIN-") (pintype "bidirectional"))
      (node (ref "C14") (pin "+") (pinfunction "+_+") (pintype "passive"))
    )
    (net (code "38") (name "MISO") (class "Default")
      (node (ref "AXO_CORE") (pin "PA6") (pinfunction "PA6_PA6") (pintype "bidirectional"))
      (node (ref "JP1") (pin "7") (pinfunction "7_7") (pintype "passive"))
      (node (ref "JP2-CONTROL") (pin "7") (pinfunction "7_7") (pintype "passive"))
      (node (ref "U$1") (pin "P$12") (pinfunction "DOUT_P$12") (pintype "bidirectional"))
      (node (ref "U$2") (pin "P$12") (pinfunction "DOUT_P$12") (pintype "bidirectional"))
    )
    (net (code "39") (name "MOSI") (class "Default")
      (node (ref "AXO_CORE") (pin "PA7") (pinfunction "PA7_PA7") (pintype "bidirectional"))
      (node (ref "JP1") (pin "6") (pinfunction "6_6") (pintype "passive"))
      (node (ref "JP2-CONTROL") (pin "6") (pinfunction "6_6") (pintype "passive"))
      (node (ref "U$1") (pin "P$11") (pinfunction "DIN_P$11") (pintype "bidirectional"))
      (node (ref "U$2") (pin "P$11") (pinfunction "DIN_P$11") (pintype "bidirectional"))
    )
    (net (code "40") (name "NSS") (class "Default")
      (node (ref "AXO_CORE") (pin "PA4") (pinfunction "PA4_PA4") (pintype "bidirectional"))
      (node (ref "JP1") (pin "9") (pinfunction "9_9") (pintype "passive"))
      (node (ref "JP2-CONTROL") (pin "9") (pinfunction "9_9") (pintype "passive"))
    )
    (net (code "41") (name "Net-(AXO_CORE-PadPB6)") (class "Default")
      (node (ref "AXO_CORE") (pin "PB6") (pinfunction "PB6_PB6") (pintype "bidirectional"))
      (node (ref "JP1") (pin "29") (pinfunction "29_29") (pintype "passive"))
      (node (ref "JP2-CONTROL") (pin "29") (pinfunction "29_29") (pintype "passive"))
    )
    (net (code "42") (name "Net-(AXO_CORE-PadPB7)") (class "Default")
      (node (ref "AXO_CORE") (pin "PB7") (pinfunction "PB7_PB7") (pintype "bidirectional"))
      (node (ref "JP1") (pin "28") (pinfunction "28_28") (pintype "passive"))
      (node (ref "JP2-CONTROL") (pin "28") (pinfunction "28_28") (pintype "passive"))
    )
    (net (code "43") (name "Net-(AXO_CORE-PadPC0)") (class "Default")
      (node (ref "AXO_CORE") (pin "PC0") (pinfunction "PC0_PC0") (pintype "bidirectional"))
      (node (ref "JP1") (pin "23") (pinfunction "23_23") (pintype "passive"))
      (node (ref "JP2-CONTROL") (pin "23") (pinfunction "23_23") (pintype "passive"))
    )
    (net (code "44") (name "Net-(AXO_CORE-PadPC1)") (class "Default")
      (node (ref "AXO_CORE") (pin "PC1") (pinfunction "PC1_PC1") (pintype "bidirectional"))
      (node (ref "JP1") (pin "22") (pinfunction "22_22") (pintype "passive"))
      (node (ref "JP2-CONTROL") (pin "22") (pinfunction "22_22") (pintype "passive"))
    )
    (net (code "45") (name "Net-(AXO_CORE-PadPC2)") (class "Default")
      (node (ref "AXO_CORE") (pin "PC2") (pinfunction "PC2_PC2") (pintype "bidirectional"))
      (node (ref "JP1") (pin "21") (pinfunction "21_21") (pintype "passive"))
      (node (ref "JP2-CONTROL") (pin "21") (pinfunction "21_21") (pintype "passive"))
    )
    (net (code "46") (name "Net-(AXO_CORE-PadPC3)") (class "Default")
      (node (ref "AXO_CORE") (pin "PC3") (pinfunction "PC3_PC3") (pintype "bidirectional"))
      (node (ref "JP1") (pin "20") (pinfunction "20_20") (pintype "passive"))
      (node (ref "JP2-CONTROL") (pin "20") (pinfunction "20_20") (pintype "passive"))
    )
    (net (code "47") (name "Net-(AXO_CORE-PadVDDA)") (class "Default")
      (node (ref "AXO_CORE") (pin "VDDA") (pinfunction "VDDA_VDDA") (pintype "bidirectional"))
      (node (ref "JP1") (pin "16") (pinfunction "16_16") (pintype "passive"))
      (node (ref "JP2-CONTROL") (pin "16") (pinfunction "16_16") (pintype "passive"))
    )
    (net (code "48") (name "Net-(AXO_CORE-PadVDDA1)") (class "Default")
      (node (ref "AXO_CORE") (pin "VDDA1") (pinfunction "VDDA1_VDDA1") (pintype "bidirectional"))
      (node (ref "JP1") (pin "10") (pinfunction "10_10") (pintype "passive"))
      (node (ref "JP2-CONTROL") (pin "10") (pinfunction "10_10") (pintype "passive"))
    )
    (net (code "49") (name "Net-(AXO_CORE-PadVDDC)") (class "Default")
      (node (ref "AXO_CORE") (pin "VDDC") (pinfunction "VDDC_VDDC") (pintype "bidirectional"))
      (node (ref "JP1") (pin "2") (pinfunction "2_2") (pintype "passive"))
      (node (ref "JP2-CONTROL") (pin "2") (pinfunction "2_2") (pintype "passive"))
    )
    (net (code "50") (name "Net-(AXO_COREB-RX)") (class "Default")
      (node (ref "AXO_CORE") (pin "UARTRX") (pinfunction "RX_UARTRX") (pintype "bidirectional"))
      (node (ref "EXT") (pin "8") (pinfunction "8_8") (pintype "passive"))
    )
    (net (code "51") (name "Net-(AXO_COREB-TX)") (class "Default")
      (node (ref "AXO_CORE") (pin "UARTTX") (pinfunction "TX_UARTTX") (pintype "bidirectional"))
      (node (ref "EXT") (pin "6") (pinfunction "6_6") (pintype "passive"))
    )
    (net (code "52") (name "Net-(C24-Pad1)") (class "Default")
      (node (ref "C24") (pin "1") (pinfunction "1_1") (pintype "passive"))
      (node (ref "D4") (pin "C") (pinfunction "C_C") (pintype "passive"))
      (node (ref "IC4") (pin "IN") (pinfunction "IN_IN") (pintype "input"))
    )
    (net (code "53") (name "Net-(C25-Pad1)") (class "Default")
      (node (ref "C25") (pin "1") (pinfunction "1_1") (pintype "passive"))
      (node (ref "IC4") (pin "OUT") (pinfunction "OUT_OUT") (pintype "passive"))
      (node (ref "L3") (pin "1") (pinfunction "1_1") (pintype "passive"))
      (node (ref "TP-5V") (pin "TP") (pinfunction "TP_TP") (pintype "input"))
    )
    (net (code "54") (name "Net-(D1-PadA)") (class "Default")
      (node (ref "D1") (pin "A") (pinfunction "A_A") (pintype "passive"))
      (node (ref "POWER") (pin "10") (pinfunction "10_10") (pintype "passive"))
      (node (ref "POWER") (pin "9") (pinfunction "9_9") (pintype "passive"))
    )
    (net (code "55") (name "Net-(D1-PadC)") (class "Default")
      (node (ref "D1") (pin "C") (pinfunction "C_C") (pintype "passive"))
      (node (ref "L1") (pin "2") (pinfunction "2_2") (pintype "passive"))
    )
    (net (code "56") (name "Net-(D2-PadA)") (class "Default")
      (node (ref "D2") (pin "A") (pinfunction "A_A") (pintype "passive"))
      (node (ref "L2") (pin "2") (pinfunction "2_2") (pintype "passive"))
    )
    (net (code "57") (name "Net-(D2-PadC)") (class "Default")
      (node (ref "D2") (pin "C") (pinfunction "C_C") (pintype "passive"))
      (node (ref "POWER") (pin "1") (pinfunction "1_1") (pintype "passive"))
      (node (ref "POWER") (pin "2") (pinfunction "2_2") (pintype "passive"))
    )
    (net (code "58") (name "Net-(IC1A--IN)") (class "Default")
      (node (ref "IC1") (pin "2") (pinfunction "-IN_2") (pintype "input"))
      (node (ref "R11") (pin "1") (pinfunction "1_1") (pintype "passive"))
      (node (ref "R5") (pin "2") (pinfunction "2_2") (pintype "passive"))
    )
    (net (code "59") (name "Net-(IC1A-OUT)") (class "Default")
      (node (ref "IC1") (pin "1") (pinfunction "OUT_1") (pintype "output"))
      (node (ref "R13") (pin "3") (pinfunction "A_3") (pintype "passive"))
      (node (ref "R5") (pin "1") (pinfunction "1_1") (pintype "passive"))
    )
    (net (code "60") (name "Net-(IC1B--IN)") (class "Default")
      (node (ref "IC1") (pin "6") (pinfunction "-IN_6") (pintype "input"))
      (node (ref "R10") (pin "1") (pinfunction "1_1") (pintype "passive"))
      (node (ref "R4") (pin "2") (pinfunction "2_2") (pintype "passive"))
    )
    (net (code "61") (name "Net-(IC1B-OUT)") (class "Default")
      (node (ref "IC1") (pin "7") (pinfunction "OUT_7") (pintype "output"))
      (node (ref "R12") (pin "3") (pinfunction "A_3") (pintype "passive"))
      (node (ref "R4") (pin "1") (pinfunction "1_1") (pintype "passive"))
    )
    (net (code "62") (name "Net-(IC1C-+IN)") (class "Default")
      (node (ref "IC1") (pin "10") (pinfunction "+IN_10") (pintype "input"))
      (node (ref "JP-AU") (pin "2") (pinfunction "2_2") (pintype "passive"))
    )
    (net (code "63") (name "Net-(IC1C--IN)") (class "Default")
      (node (ref "IC1") (pin "9") (pinfunction "-IN_9") (pintype "input"))
      (node (ref "R23") (pin "2") (pinfunction "2_2") (pintype "passive"))
      (node (ref "R27") (pin "1") (pinfunction "1_1") (pintype "passive"))
    )
    (net (code "64") (name "Net-(IC1C-OUT)") (class "Default")
      (node (ref "IC1") (pin "8") (pinfunction "OUT_8") (pintype "output"))
      (node (ref "R20") (pin "2") (pinfunction "2_2") (pintype "passive"))
      (node (ref "R23") (pin "1") (pinfunction "1_1") (pintype "passive"))
    )
    (net (code "65") (name "Net-(IC1D-+IN)") (class "Default")
      (node (ref "IC1") (pin "12") (pinfunction "+IN_12") (pintype "input"))
      (node (ref "JP-AU") (pin "1") (pinfunction "1_1") (pintype "passive"))
    )
    (net (code "66") (name "Net-(IC1D--IN)") (class "Default")
      (node (ref "IC1") (pin "13") (pinfunction "-IN_13") (pintype "input"))
      (node (ref "R22") (pin "2") (pinfunction "2_2") (pintype "passive"))
      (node (ref "R26") (pin "1") (pinfunction "1_1") (pintype "passive"))
    )
    (net (code "67") (name "Net-(IC1D-OUT)") (class "Default")
      (node (ref "IC1") (pin "14") (pinfunction "OUT_14") (pintype "output"))
      (node (ref "R21") (pin "2") (pinfunction "2_2") (pintype "passive"))
      (node (ref "R22") (pin "1") (pinfunction "1_1") (pintype "passive"))
    )
    (net (code "68") (name "Net-(IC2A--IN)") (class "Default")
      (node (ref "C16") (pin "1") (pinfunction "1_1") (pintype "passive"))
      (node (ref "IC2") (pin "2") (pinfunction "-IN_2") (pintype "input"))
      (node (ref "R15") (pin "1") (pinfunction "1_1") (pintype "passive"))
      (node (ref "R17") (pin "2") (pinfunction "2_2") (pintype "passive"))
      (node (ref "R19") (pin "1") (pinfunction "1_1") (pintype "passive"))
    )
    (net (code "69") (name "Net-(IC2B--IN)") (class "Default")
      (node (ref "C12") (pin "1") (pinfunction "1_1") (pintype "passive"))
      (node (ref "IC2") (pin "6") (pinfunction "-IN_6") (pintype "input"))
      (node (ref "R3") (pin "1") (pinfunction "1_1") (pintype "passive"))
      (node (ref "R7") (pin "2") (pinfunction "2_2") (pintype "passive"))
      (node (ref "R9") (pin "1") (pinfunction "1_1") (pintype "passive"))
    )
    (net (code "70") (name "Net-(IC2C--IN)") (class "Default")
      (node (ref "C15") (pin "1") (pinfunction "1_1") (pintype "passive"))
      (node (ref "IC2") (pin "9") (pinfunction "-IN_9") (pintype "input"))
      (node (ref "R14") (pin "1") (pinfunction "1_1") (pintype "passive"))
      (node (ref "R16") (pin "2") (pinfunction "2_2") (pintype "passive"))
      (node (ref "R18") (pin "1") (pinfunction "1_1") (pintype "passive"))
    )
    (net (code "71") (name "Net-(IC2D--IN)") (class "Default")
      (node (ref "C11") (pin "1") (pinfunction "1_1") (pintype "passive"))
      (node (ref "IC2") (pin "13") (pinfunction "-IN_13") (pintype "input"))
      (node (ref "R2") (pin "1") (pinfunction "1_1") (pintype "passive"))
      (node (ref "R6") (pin "2") (pinfunction "2_2") (pintype "passive"))
      (node (ref "R8") (pin "1") (pinfunction "1_1") (pintype "passive"))
    )
    (net (code "72") (name "Net-(IC3A--IN)") (class "Default")
      (node (ref "C19") (pin "1") (pinfunction "1_1") (pintype "passive"))
      (node (ref "IC3") (pin "2") (pinfunction "-IN_2") (pintype "input"))
      (node (ref "R34") (pin "1") (pinfunction "1_1") (pintype "passive"))
      (node (ref "R36") (pin "2") (pinfunction "2_2") (pintype "passive"))
      (node (ref "R38") (pin "1") (pinfunction "1_1") (pintype "passive"))
    )
    (net (code "73") (name "Net-(IC3B--IN)") (class "Default")
      (node (ref "C17") (pin "1") (pinfunction "1_1") (pintype "passive"))
      (node (ref "IC3") (pin "6") (pinfunction "-IN_6") (pintype "input"))
      (node (ref "R24") (pin "1") (pinfunction "1_1") (pintype "passive"))
      (node (ref "R28") (pin "2") (pinfunction "2_2") (pintype "passive"))
      (node (ref "R30") (pin "1") (pinfunction "1_1") (pintype "passive"))
    )
    (net (code "74") (name "Net-(IC3C--IN)") (class "Default")
      (node (ref "C18") (pin "1") (pinfunction "1_1") (pintype "passive"))
      (node (ref "IC3") (pin "9") (pinfunction "-IN_9") (pintype "input"))
      (node (ref "R25") (pin "1") (pinfunction "1_1") (pintype "passive"))
      (node (ref "R29") (pin "2") (pinfunction "2_2") (pintype "passive"))
      (node (ref "R31") (pin "1") (pinfunction "1_1") (pintype "passive"))
    )
    (net (code "75") (name "Net-(IC3D--IN)") (class "Default")
      (node (ref "C20") (pin "1") (pinfunction "1_1") (pintype "passive"))
      (node (ref "IC3") (pin "13") (pinfunction "-IN_13") (pintype "input"))
      (node (ref "R35") (pin "1") (pinfunction "1_1") (pintype "passive"))
      (node (ref "R37") (pin "2") (pinfunction "2_2") (pintype "passive"))
      (node (ref "R39") (pin "1") (pinfunction "1_1") (pintype "passive"))
    )
    (net (code "76") (name "Net-(R12-S)") (class "Default")
      (node (ref "AU-IN") (pin "2") (pinfunction "2_2") (pintype "passive"))
      (node (ref "C13") (pin "-") (pinfunction "-_-") (pintype "passive"))
      (node (ref "R12") (pin "2") (pinfunction "S_2") (pintype "passive"))
    )
    (net (code "77") (name "Net-(R13-S)") (class "Default")
      (node (ref "AU-IN") (pin "1") (pinfunction "1_1") (pintype "passive"))
      (node (ref "C14") (pin "-") (pinfunction "-_-") (pintype "passive"))
      (node (ref "R13") (pin "2") (pinfunction "S_2") (pintype "passive"))
    )
    (net (code "78") (name "Net-(R32-A)") (class "Default")
      (node (ref "R26") (pin "2") (pinfunction "2_2") (pintype "passive"))
      (node (ref "R32") (pin "3") (pinfunction "A_3") (pintype "passive"))
    )
    (net (code "79") (name "Net-(R33-A)") (class "Default")
      (node (ref "R27") (pin "2") (pinfunction "2_2") (pintype "passive"))
      (node (ref "R33") (pin "3") (pinfunction "A_3") (pintype "passive"))
    )
    (net (code "80") (name "OUT1") (class "Default")
      (node (ref "JP-AUDIO") (pin "3") (pinfunction "3_3") (pintype "passive"))
      (node (ref "JP-AUDIO") (pin "4") (pinfunction "4_4") (pintype "passive"))
      (node (ref "R21") (pin "1") (pinfunction "1_1") (pintype "passive"))
    )
    (net (code "81") (name "OUT2") (class "Default")
      (node (ref "JP-AUDIO") (pin "5") (pinfunction "5_5") (pintype "passive"))
      (node (ref "JP-AUDIO") (pin "6") (pinfunction "6_6") (pintype "passive"))
      (node (ref "R20") (pin "1") (pinfunction "1_1") (pintype "passive"))
    )
    (net (code "82") (name "PA0{slash}PWM") (class "Default")
      (node (ref "AXO_CORE") (pin "PA0") (pinfunction "PA0_PA0") (pintype "bidirectional"))
      (node (ref "JP1") (pin "15") (pinfunction "15_15") (pintype "passive"))
      (node (ref "JP2-CONTROL") (pin "15") (pinfunction "15_15") (pintype "passive"))
    )
    (net (code "83") (name "PA1{slash}PWM") (class "Default")
      (node (ref "AXO_CORE") (pin "PA1") (pinfunction "PA1_PA1") (pintype "bidirectional"))
      (node (ref "JP1") (pin "14") (pinfunction "14_14") (pintype "passive"))
      (node (ref "JP2-CONTROL") (pin "14") (pinfunction "14_14") (pintype "passive"))
    )
    (net (code "84") (name "PA2{slash}TX") (class "Default")
      (node (ref "AXO_CORE") (pin "PA2") (pinfunction "PA2_PA2") (pintype "bidirectional"))
      (node (ref "JP1") (pin "13") (pinfunction "13_13") (pintype "passive"))
      (node (ref "JP2-CONTROL") (pin "13") (pinfunction "13_13") (pintype "passive"))
    )
    (net (code "85") (name "PA3{slash}RX") (class "Default")
      (node (ref "AXO_CORE") (pin "PA3") (pinfunction "PA3_PA3") (pintype "bidirectional"))
      (node (ref "JP1") (pin "12") (pinfunction "12_12") (pintype "passive"))
      (node (ref "JP2-CONTROL") (pin "12") (pinfunction "12_12") (pintype "passive"))
    )
    (net (code "86") (name "PB0{slash}PWM") (class "Default")
      (node (ref "AXO_CORE") (pin "PB0") (pinfunction "PB0_PB0") (pintype "bidirectional"))
      (node (ref "JP1") (pin "5") (pinfunction "5_5") (pintype "passive"))
      (node (ref "JP2-CONTROL") (pin "5") (pinfunction "5_5") (pintype "passive"))
    )
    (net (code "87") (name "PB1{slash}PWM") (class "Default")
      (node (ref "AXO_CORE") (pin "PB1") (pinfunction "PB1_PB1") (pintype "bidirectional"))
      (node (ref "JP1") (pin "4") (pinfunction "4_4") (pintype "passive"))
      (node (ref "JP2-CONTROL") (pin "4") (pinfunction "4_4") (pintype "passive"))
    )
    (net (code "88") (name "RIN+") (class "Default")
      (node (ref "AXO_CORE") (pin "RIN+") (pinfunction "RIN+_RIN+") (pintype "bidirectional"))
    )
    (net (code "89") (name "RIN-") (class "Default")
      (node (ref "AUDIORAW") (pin "3") (pinfunction "3_3") (pintype "passive"))
      (node (ref "AXO_CORE") (pin "RIN-") (pinfunction "RIN-_RIN-") (pintype "bidirectional"))
      (node (ref "C13") (pin "+") (pinfunction "+_+") (pintype "passive"))
    )
    (net (code "90") (name "SCK") (class "Default")
      (node (ref "AXO_CORE") (pin "PA5") (pinfunction "PA5_PA5") (pintype "bidirectional"))
      (node (ref "JP1") (pin "8") (pinfunction "8_8") (pintype "passive"))
      (node (ref "JP2-CONTROL") (pin "8") (pinfunction "8_8") (pintype "passive"))
      (node (ref "U$1") (pin "P$13") (pinfunction "CLK_P$13") (pintype "bidirectional"))
      (node (ref "U$2") (pin "P$13") (pinfunction "CLK_P$13") (pintype "bidirectional"))
    )
    (net (code "91") (name "SCL") (class "Default")
      (node (ref "AXO_CORE") (pin "PB8") (pinfunction "PB8_PB8") (pintype "bidirectional"))
      (node (ref "EXT") (pin "5") (pinfunction "5_5") (pintype "passive"))
      (node (ref "JP1") (pin "27") (pinfunction "27_27") (pintype "passive"))
      (node (ref "JP2-CONTROL") (pin "27") (pinfunction "27_27") (pintype "passive"))
    )
    (net (code "92") (name "SDA") (class "Default")
      (node (ref "AXO_CORE") (pin "PB9") (pinfunction "PB9_PB9") (pintype "bidirectional"))
      (node (ref "EXT") (pin "7") (pinfunction "7_7") (pintype "passive"))
      (node (ref "JP1") (pin "26") (pinfunction "26_26") (pintype "passive"))
      (node (ref "JP2-CONTROL") (pin "26") (pinfunction "26_26") (pintype "passive"))
    )
    (net (code "93") (name "VBUS") (class "Default")
      (node (ref "AXO_CORE") (pin "VBUS") (pinfunction "VBUS_VBUS") (pintype "bidirectional"))
      (node (ref "C23") (pin "1") (pinfunction "1_1") (pintype "passive"))
      (node (ref "D3") (pin "C") (pinfunction "C_C") (pintype "passive"))
      (node (ref "R40") (pin "2") (pinfunction "2_2") (pintype "passive"))
      (node (ref "TP-VBUS") (pin "TP") (pinfunction "TP_TP") (pintype "input"))
    )
    (net (code "94") (name "VCC") (class "Default")
      (node (ref "C21") (pin "+") (pinfunction "+_+") (pintype "passive"))
      (node (ref "C7") (pin "1") (pinfunction "1_1") (pintype "passive"))
      (node (ref "D4") (pin "A") (pinfunction "A_A") (pintype "passive"))
      (node (ref "IC1") (pin "4") (pinfunction "V+_4") (pintype "power_in"))
      (node (ref "L1") (pin "1") (pinfunction "1_1") (pintype "passive"))
      (node (ref "R40") (pin "1") (pinfunction "1_1") (pintype "passive"))
    )
    (net (code "95") (name "VDD") (class "Default")
      (node (ref "AXO_CORE") (pin "VDD1") (pinfunction "VDD1_VDD1") (pintype "bidirectional"))
      (node (ref "C1") (pin "2") (pinfunction "2_2") (pintype "passive"))
      (node (ref "C2") (pin "2") (pinfunction "2_2") (pintype "passive"))
      (node (ref "JP1") (pin "24") (pinfunction "24_24") (pintype "passive"))
      (node (ref "JP2-CONTROL") (pin "24") (pinfunction "24_24") (pintype "passive"))
      (node (ref "R1") (pin "1") (pinfunction "1_1") (pintype "passive"))
      (node (ref "TP-VADC") (pin "TP") (pinfunction "TP_TP") (pintype "input"))
      (node (ref "U$1") (pin "P$16") (pinfunction "VDD_P$16") (pintype "bidirectional"))
      (node (ref "U$2") (pin "P$16") (pinfunction "VDD_P$16") (pintype "bidirectional"))
    )
    (net (code "96") (name "VDD+") (class "Default")
      (node (ref "AXO_CORE") (pin "VDD") (pinfunction "VDD_VDD") (pintype "bidirectional"))
      (node (ref "EXT") (pin "1") (pinfunction "1_1") (pintype "passive"))
      (node (ref "EXT") (pin "2") (pinfunction "2_2") (pintype "passive"))
      (node (ref "JP1") (pin "30") (pinfunction "30_30") (pintype "passive"))
      (node (ref "JP2-CONTROL") (pin "30") (pinfunction "30_30") (pintype "passive"))
    )
    (net (code "97") (name "VDDAA") (class "Default")
      (node (ref "C3") (pin "1") (pinfunction "1_1") (pintype "passive"))
      (node (ref "C4") (pin "+") (pinfunction "+_+") (pintype "passive"))
      (node (ref "C5") (pin "1") (pinfunction "1_1") (pintype "passive"))
      (node (ref "C6") (pin "+") (pinfunction "+_+") (pintype "passive"))
      (node (ref "C8") (pin "1") (pinfunction "1_1") (pintype "passive"))
      (node (ref "C9") (pin "1") (pinfunction "1_1") (pintype "passive"))
      (node (ref "IC2") (pin "4") (pinfunction "V+_4") (pintype "power_in"))
      (node (ref "IC3") (pin "4") (pinfunction "V+_4") (pintype "power_in"))
      (node (ref "JP-POT") (pin "10") (pinfunction "10_10") (pintype "passive"))
      (node (ref "R1") (pin "2") (pinfunction "2_2") (pintype "passive"))
      (node (ref "U$1") (pin "P$15") (pinfunction "VREF_P$15") (pintype "bidirectional"))
      (node (ref "U$2") (pin "P$15") (pinfunction "VREF_P$15") (pintype "bidirectional"))
    )
    (net (code "98") (name "VEE") (class "Default")
      (node (ref "C10") (pin "2") (pinfunction "2_2") (pintype "passive"))
      (node (ref "C22") (pin "-") (pinfunction "-_-") (pintype "passive"))
      (node (ref "IC1") (pin "11") (pinfunction "V-_11") (pintype "power_in"))
      (node (ref "L2") (pin "1") (pinfunction "1_1") (pintype "passive"))
      (node (ref "R41") (pin "1") (pinfunction "1_1") (pintype "passive"))
    )
  )
)
